# motor.net
KiCad netlist of a schematic drawn in Altium Designer
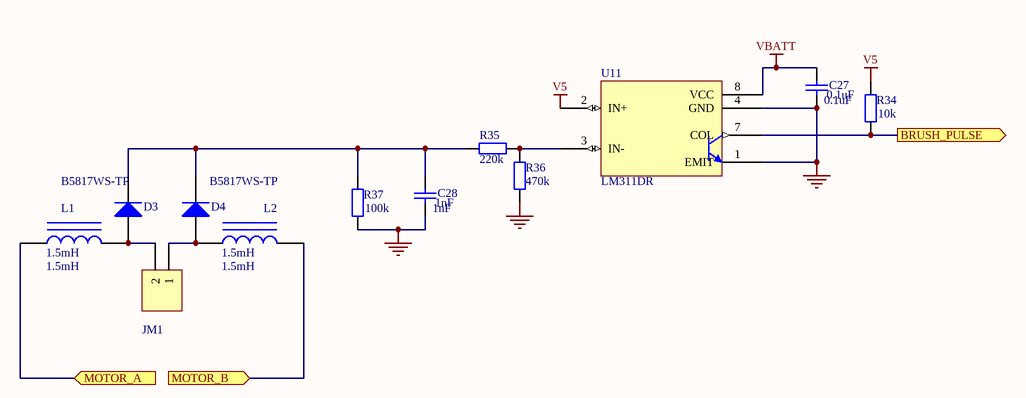
[diagram p0: motor.SchDoc]

(export (version "E")
  (design (tool "Eeschema 10.0.6"))
  (components
    (comp (ref "C27")
      (value "0.1uF")
      (footprint "CAPC2012L")
      (description "Capacitor")
      (fields (field (name "ALTIUM_VALUE") "0.1uF") (field (name "PUBLISHER") "Altium Limited"))
      (libsource (lib "*") (part "Cap"))
    )
    (comp (ref "C28")
      (value "1nF")
      (footprint "CAPC1608L")
      (description "Capacitor")
      (fields (field (name "ALTIUM_VALUE") "1nF") (field (name "PUBLISHER") "Altium Limited"))
      (libsource (lib "*") (part "Cap"))
    )
    (comp (ref "D3")
      (value "B5817WS-TP")
      (footprint "SOD_323")
      (libsource (lib "components") (part "B5817WS-TP"))
    )
    (comp (ref "D4")
      (value "B5817WS-TP")
      (footprint "SOD_323")
      (libsource (lib "components") (part "B5817WS-TP"))
    )
    (comp (ref "JM1")
      (value "~")
      (footprint "HDR1X2H")
      (description "Header, 2-Pin")
      (fields (field (name "PUBLISHER") "Altium Limited"))
      (libsource (lib "*") (part "Header 2"))
    )
    (comp (ref "L1")
      (value "1.5mH")
      (footprint "InductorThruHole")
      (description "Magnetic-Core Inductor")
      (fields (field (name "ALTIUM_VALUE") "1.5mH") (field (name "PUBLISHER") "Altium Limited"))
      (libsource (lib "Miscellaneous Devices") (part "Inductor Iron"))
    )
    (comp (ref "L2")
      (value "1.5mH")
      (footprint "InductorThruHole")
      (description "Magnetic-Core Inductor")
      (fields (field (name "ALTIUM_VALUE") "1.5mH") (field (name "PUBLISHER") "Altium Limited"))
      (libsource (lib "Miscellaneous Devices") (part "Inductor Iron"))
    )
    (comp (ref "R34")
      (value "10k")
      (footprint "RESC1608L")
      (description "Resistor")
      (fields (field (name "PUBLISHER") "Altium Limited"))
      (libsource (lib "") (part "Res2_1"))
    )
    (comp (ref "R35")
      (value "220k")
      (footprint "RESC1608L")
      (description "Resistor")
      (fields (field (name "PUBLISHER") "Altium Limited"))
      (libsource (lib "*") (part "Res2"))
    )
    (comp (ref "R36")
      (value "470k")
      (footprint "RESC1608L")
      (description "Resistor")
      (fields (field (name "PUBLISHER") "Altium Limited"))
      (libsource (lib "") (part "Res2_2"))
    )
    (comp (ref "R37")
      (value "100k")
      (footprint "RESC1608L")
      (description "Resistor")
      (fields (field (name "PUBLISHER") "Altium Limited"))
      (libsource (lib "") (part "Res2_1"))
    )
    (comp (ref "U11") (value "LM311DR") (footprint "LM311DR") (libsource (lib "components") (part "LM311DR")))
  )
  (nets
    (net (code "1") (name "/BRUSH_PULSE") (class "Default")
      (node (ref "R34") (pin "2") (pinfunction "2_2") (pintype "passive"))
      (node (ref "U11") (pin "7") (pinfunction "COL_7") (pintype "output"))
    )
    (net (code "2") (name "/MOTOR_A") (class "Default")
      (node (ref "L1") (pin "1") (pinfunction "1_1") (pintype "passive"))
    )
    (net (code "3") (name "/MOTOR_B") (class "Default")
      (node (ref "L2") (pin "2") (pinfunction "2_2") (pintype "passive"))
    )
    (net (code "4") (name "GND") (class "Default")
      (node (ref "C27") (pin "2") (pinfunction "2_2") (pintype "passive"))
      (node (ref "C28") (pin "2") (pinfunction "2_2") (pintype "passive"))
      (node (ref "R36") (pin "1") (pinfunction "1_1") (pintype "passive"))
      (node (ref "R37") (pin "2") (pinfunction "2_2") (pintype "passive"))
      (node (ref "U11") (pin "1") (pinfunction "EMIT_1") (pintype "power_in"))
      (node (ref "U11") (pin "4") (pinfunction "GND_4") (pintype "power_in"))
    )
    (net (code "5") (name "Net-(C28-Pad1)") (class "Default")
      (node (ref "C28") (pin "1") (pinfunction "1_1") (pintype "passive"))
      (node (ref "D3") (pin "2") (pinfunction "2_2") (pintype "passive"))
      (node (ref "D4") (pin "2") (pinfunction "2_2") (pintype "passive"))
      (node (ref "R35") (pin "1") (pinfunction "1_1") (pintype "passive"))
      (node (ref "R37") (pin "1") (pinfunction "1_1") (pintype "passive"))
    )
    (net (code "6") (name "Net-(D3-Pad1)") (class "Default")
      (node (ref "D3") (pin "1") (pinfunction "1_1") (pintype "passive"))
      (node (ref "JM1") (pin "2") (pinfunction "2_2") (pintype "passive"))
      (node (ref "L1") (pin "2") (pinfunction "2_2") (pintype "passive"))
    )
    (net (code "7") (name "Net-(D4-Pad1)") (class "Default")
      (node (ref "D4") (pin "1") (pinfunction "1_1") (pintype "passive"))
      (node (ref "JM1") (pin "1") (pinfunction "1_1") (pintype "passive"))
      (node (ref "L2") (pin "1") (pinfunction "1_1") (pintype "passive"))
    )
    (net (code "8") (name "Net-(U11-IN-)") (class "Default")
      (node (ref "R35") (pin "2") (pinfunction "2_2") (pintype "passive"))
      (node (ref "R36") (pin "2") (pinfunction "2_2") (pintype "passive"))
      (node (ref "U11") (pin "3") (pinfunction "IN-_3") (pintype "bidirectional"))
    )
    (net (code "9") (name "V5") (class "Default")
      (node (ref "R34") (pin "1") (pinfunction "1_1") (pintype "passive"))
      (node (ref "U11") (pin "2") (pinfunction "IN+_2") (pintype "bidirectional"))
    )
    (net (code "10") (name "VBATT") (class "Default")
      (node (ref "C27") (pin "1") (pinfunction "1_1") (pintype "passive"))
      (node (ref "U11") (pin "8") (pinfunction "VCC_8") (pintype "power_in"))
    )
  )
)
